# PIC32.net
KiCad netlist of a schematic drawn in Altium Designer
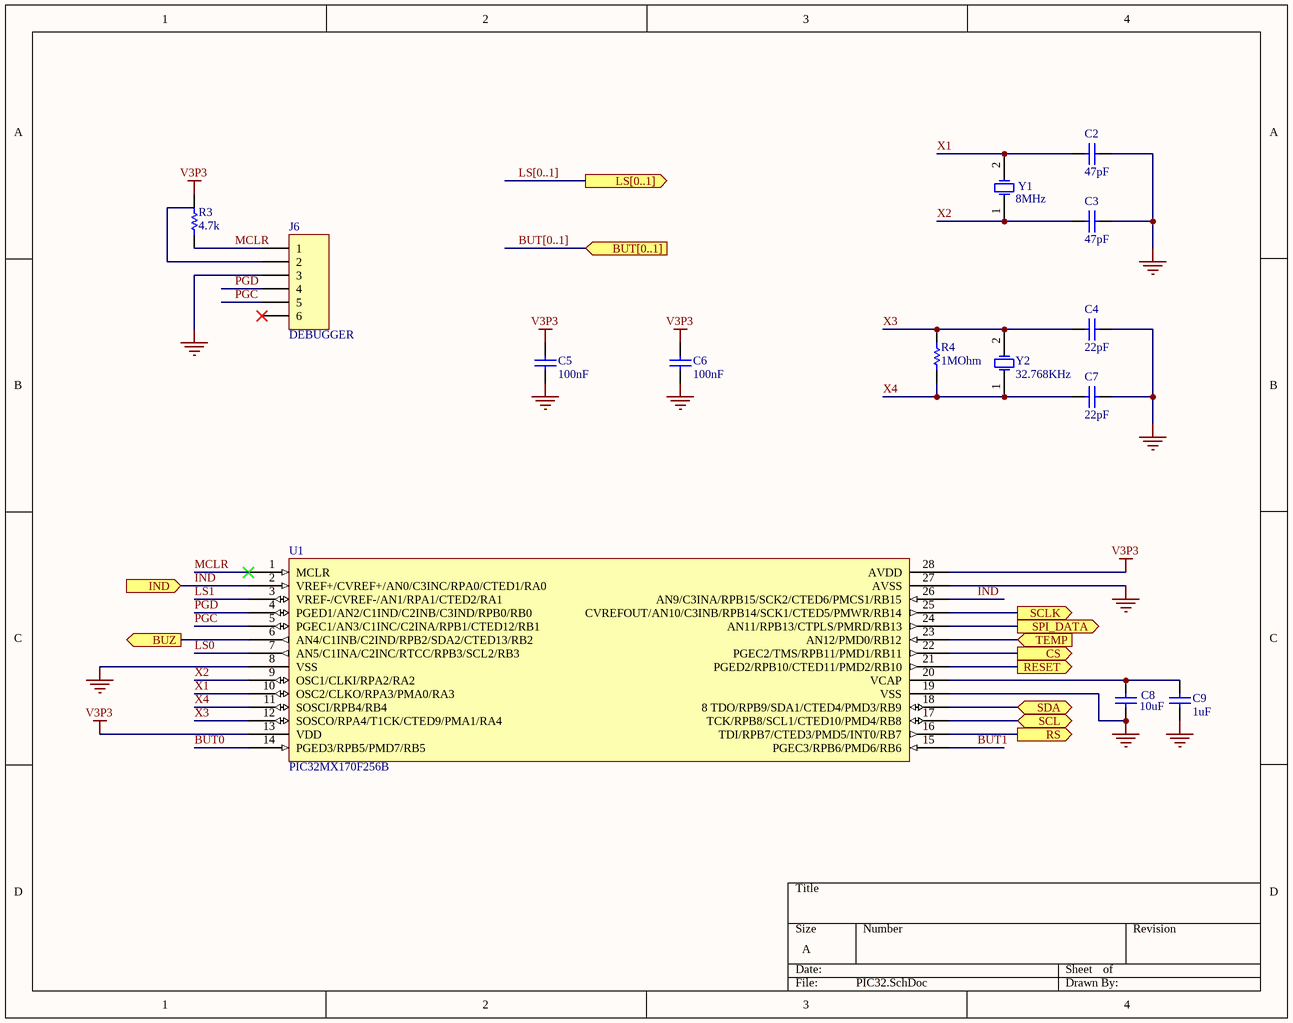
[diagram p0: PIC32.SchDoc]

(export (version "E")
  (design (tool "Eeschema 10.0.6"))
  (components
    (comp (ref "C2")
      (value "47pF")
      (footprint "CAPACITOR")
      (description "Capacitor")
      (fields (field (name "PUBLISHER") "Altium Limited"))
      (libsource (lib "Miscellaneous Devices") (part "Cap"))
    )
    (comp (ref "C3")
      (value "47pF")
      (footprint "CAPACITOR")
      (description "Capacitor")
      (fields (field (name "PUBLISHER") "Altium Limited"))
      (libsource (lib "Miscellaneous Devices") (part "Cap"))
    )
    (comp (ref "C4")
      (value "22pF")
      (footprint "CAPACITOR")
      (description "Capacitor")
      (fields (field (name "PUBLISHER") "Altium Limited"))
      (libsource (lib "Miscellaneous Devices") (part "Cap"))
    )
    (comp (ref "C5")
      (value "100nF")
      (footprint "CAPACITOR")
      (description "Capacitor")
      (fields (field (name "PUBLISHER") "Altium Limited"))
      (libsource (lib "Miscellaneous Devices") (part "Cap"))
    )
    (comp (ref "C6")
      (value "100nF")
      (footprint "CAPACITOR")
      (description "Capacitor")
      (fields (field (name "PUBLISHER") "Altium Limited"))
      (libsource (lib "Miscellaneous Devices") (part "Cap"))
    )
    (comp (ref "C7")
      (value "22pF")
      (footprint "CAPACITOR")
      (description "Capacitor")
      (fields (field (name "PUBLISHER") "Altium Limited"))
      (libsource (lib "Miscellaneous Devices") (part "Cap"))
    )
    (comp (ref "C8")
      (value "10uF")
      (footprint "CAPACITOR")
      (description "Capacitor")
      (fields (field (name "PUBLISHER") "Altium Limited"))
      (libsource (lib "Miscellaneous Devices") (part "Cap"))
    )
    (comp (ref "C9")
      (value "1uF")
      (footprint "CAPACITOR")
      (description "Capacitor")
      (fields (field (name "PUBLISHER") "Altium Limited"))
      (libsource (lib "Miscellaneous Devices") (part "Cap"))
    )
    (comp (ref "J6")
      (value "DEBUGGER")
      (footprint "DEBUG")
      (description "DEB Connector")
      (fields (field (name "PUBLISHER") "Altium Limited"))
      (libsource (lib "Miscellaneous Connectors") (part "Header 6"))
    )
    (comp (ref "R3")
      (value "4.7k")
      (footprint "Resistor")
      (description "Resistor")
      (fields (field (name "PUBLISHER") "Altium Limited"))
      (libsource (lib "Miscellaneous Devices") (part "Res1"))
    )
    (comp (ref "R4")
      (value "1MOhm")
      (footprint "Resistor")
      (description "Resistor")
      (fields (field (name "PUBLISHER") "Altium Limited"))
      (libsource (lib "Miscellaneous Devices") (part "Res1"))
    )
    (comp (ref "U1")
      (value "PIC32MX170F256B")
      (footprint "PIC32")
      (description "PIC32")
      (libsource (lib "Klotz") (part "PIC32MX170F256B"))
    )
    (comp (ref "Y1")
      (value "8MHz")
      (footprint "OSC1")
      (description "Crystal Oscillator")
      (fields (field (name "PUBLISHER") "Altium Limited"))
      (libsource (lib "Miscellaneous Devices") (part "XTAL"))
    )
    (comp (ref "Y2")
      (value "32.768KHz")
      (footprint "OSC2")
      (description "Crystal Oscillator")
      (fields (field (name "PUBLISHER") "Altium Limited"))
      (libsource (lib "Miscellaneous Devices") (part "XTAL"))
    )
  )
  (nets
    (net (code "1") (name "/BUT0") (class "Default")
      (node (ref "U1") (pin "14") (pinfunction "PGED3/RPB5/PMD7/RB5_14") (pintype "input"))
    )
    (net (code "2") (name "/BUT1") (class "Default")
      (node (ref "U1") (pin "15") (pinfunction "PGEC3/RPB6/PMD6/RB6_15") (pintype "input"))
    )
    (net (code "4") (name "/BUZ") (class "Default")
      (node (ref "U1") (pin "6") (pinfunction "AN4/C1INB/C2IND/RPB2/SDA2/CTED13/RB2_6") (pintype "output"))
    )
    (net (code "5") (name "/CS") (class "Default")
      (node (ref "U1") (pin "22") (pinfunction "PGEC2/TMS/RPB11/PMD1/RB11_22") (pintype "output"))
    )
    (net (code "6") (name "/IND") (class "Default")
      (node (ref "U1") (pin "2") (pinfunction "VREF+/CVREF+/AN0/C3INC/RPA0/CTED1/RA0_2") (pintype "input"))
      (node (ref "U1") (pin "26") (pinfunction "AN9/C3INA/RPB15/SCK2/CTED6/PMCS1/RB15_26") (pintype "input"))
    )
    (net (code "7") (name "/LS0") (class "Default")
      (node (ref "U1") (pin "7") (pinfunction "AN5/C1INA/C2INC/RTCC/RPB3/SCL2/RB3_7") (pintype "output"))
    )
    (net (code "8") (name "/LS1") (class "Default")
      (node (ref "U1") (pin "3") (pinfunction "VREF-/CVREF-/AN1/RPA1/CTED2/RA1_3") (pintype "bidirectional"))
    )
    (net (code "10") (name "/MCLR") (class "Default")
      (node (ref "J6") (pin "1") (pinfunction "1_1") (pintype "passive"))
      (node (ref "R3") (pin "2") (pinfunction "2_2") (pintype "passive"))
      (node (ref "U1") (pin "1") (pinfunction "MCLR_1") (pintype "input"))
    )
    (net (code "11") (name "/PGC") (class "Default")
      (node (ref "J6") (pin "5") (pinfunction "5_5") (pintype "passive"))
      (node (ref "U1") (pin "5") (pinfunction "PGEC1/AN3/C1INC/C2INA/RPB1/CTED12/RB1_5") (pintype "bidirectional"))
    )
    (net (code "12") (name "/PGD") (class "Default")
      (node (ref "J6") (pin "4") (pinfunction "4_4") (pintype "passive"))
      (node (ref "U1") (pin "4") (pinfunction "PGED1/AN2/C1IND/C2INB/C3IND/RPB0/RB0_4") (pintype "bidirectional"))
    )
    (net (code "13") (name "/RESET") (class "Default")
      (node (ref "U1") (pin "21") (pinfunction "PGED2/RPB10/CTED11/PMD2/RB10_21") (pintype "output"))
    )
    (net (code "14") (name "/RS") (class "Default")
      (node (ref "U1") (pin "16") (pinfunction "TDI/RPB7/CTED3/PMD5/INT0/RB7_16") (pintype "output"))
    )
    (net (code "15") (name "/SCL") (class "Default")
      (node (ref "U1") (pin "17") (pinfunction "TCK/RPB8/SCL1/CTED10/PMD4/RB8_17") (pintype "bidirectional"))
    )
    (net (code "16") (name "/SCLK") (class "Default")
      (node (ref "U1") (pin "25") (pinfunction "CVREFOUT/AN10/C3INB/RPB14/SCK1/CTED5/PMWR/RB14_25") (pintype "output"))
    )
    (net (code "17") (name "/SDA") (class "Default")
      (node (ref "U1") (pin "18") (pinfunction "8_TDO/RPB9/SDA1/CTED4/PMD3/RB9_18") (pintype "bidirectional"))
    )
    (net (code "18") (name "/SPI_DATA") (class "Default")
      (node (ref "U1") (pin "24") (pinfunction "AN11/RPB13/CTPLS/PMRD/RB13_24") (pintype "output"))
    )
    (net (code "19") (name "/TEMP") (class "Default")
      (node (ref "U1") (pin "23") (pinfunction "AN12/PMD0/RB12_23") (pintype "input"))
    )
    (net (code "20") (name "/X1") (class "Default")
      (node (ref "C2") (pin "1") (pinfunction "1_1") (pintype "passive"))
      (node (ref "U1") (pin "10") (pinfunction "OSC2/CLKO/RPA3/PMA0/RA3_10") (pintype "bidirectional"))
      (node (ref "Y1") (pin "2") (pinfunction "OSC2_2") (pintype "passive"))
    )
    (net (code "21") (name "/X2") (class "Default")
      (node (ref "C3") (pin "1") (pinfunction "1_1") (pintype "passive"))
      (node (ref "U1") (pin "9") (pinfunction "OSC1/CLKI/RPA2/RA2_9") (pintype "bidirectional"))
      (node (ref "Y1") (pin "1") (pinfunction "OSC1_1") (pintype "passive"))
    )
    (net (code "22") (name "/X3") (class "Default")
      (node (ref "C4") (pin "1") (pinfunction "1_1") (pintype "passive"))
      (node (ref "R4") (pin "1") (pinfunction "1_1") (pintype "passive"))
      (node (ref "U1") (pin "12") (pinfunction "SOSCO/RPA4/T1CK/CTED9/PMA1/RA4_12") (pintype "bidirectional"))
      (node (ref "Y2") (pin "2") (pinfunction "OSC2_2") (pintype "passive"))
    )
    (net (code "23") (name "/X4") (class "Default")
      (node (ref "C7") (pin "1") (pinfunction "1_1") (pintype "passive"))
      (node (ref "R4") (pin "2") (pinfunction "2_2") (pintype "passive"))
      (node (ref "U1") (pin "11") (pinfunction "SOSCI/RPB4/RB4_11") (pintype "bidirectional"))
      (node (ref "Y2") (pin "1") (pinfunction "OSC1_1") (pintype "passive"))
    )
    (net (code "24") (name "GND") (class "Default")
      (node (ref "C2") (pin "2") (pinfunction "2_2") (pintype "passive"))
      (node (ref "C3") (pin "2") (pinfunction "2_2") (pintype "passive"))
      (node (ref "C4") (pin "2") (pinfunction "2_2") (pintype "passive"))
      (node (ref "C5") (pin "1") (pinfunction "1_1") (pintype "passive"))
      (node (ref "C6") (pin "1") (pinfunction "1_1") (pintype "passive"))
      (node (ref "C7") (pin "2") (pinfunction "2_2") (pintype "passive"))
      (node (ref "C8") (pin "1") (pinfunction "1_1") (pintype "passive"))
      (node (ref "C9") (pin "1") (pinfunction "1_1") (pintype "passive"))
      (node (ref "J6") (pin "3") (pinfunction "3_3") (pintype "passive"))
      (node (ref "U1") (pin "19") (pinfunction "VSS_19") (pintype "power_in"))
      (node (ref "U1") (pin "27") (pinfunction "AVSS_27") (pintype "power_in"))
      (node (ref "U1") (pin "8") (pinfunction "VSS_8") (pintype "power_in"))
    )
    (net (code "25") (name "Net-(U1-VCAP)") (class "Default")
      (node (ref "C8") (pin "2") (pinfunction "2_2") (pintype "passive"))
      (node (ref "C9") (pin "2") (pinfunction "2_2") (pintype "passive"))
      (node (ref "U1") (pin "20") (pinfunction "VCAP_20") (pintype "power_in"))
    )
    (net (code "26") (name "V3P3") (class "Default")
      (node (ref "C5") (pin "2") (pinfunction "2_2") (pintype "passive"))
      (node (ref "C6") (pin "2") (pinfunction "2_2") (pintype "passive"))
      (node (ref "R3") (pin "1") (pinfunction "1_1") (pintype "passive"))
      (node (ref "U1") (pin "13") (pinfunction "VDD_13") (pintype "power_in"))
      (node (ref "U1") (pin "28") (pinfunction "AVDD_28") (pintype "power_in"))
    )
    (net (code "27") (name "unconnected-(J6-Pad2)") (class "Default")
      (node (ref "J6") (pin "2") (pinfunction "2_2") (pintype "passive"))
    )
    (net (code "28") (name "unconnected-(J6-Pad6)") (class "Default")
      (node (ref "J6") (pin "6") (pinfunction "6_6") (pintype "passive+no_connect"))
    )
  )
)
